# 8085.net
KiCad netlist of a schematic drawn in EAGLE
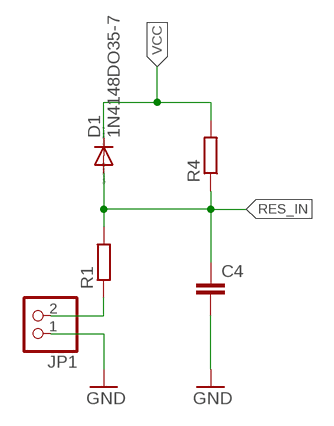
[diagram p0: schematic, sheet 1, part 1 of 3]
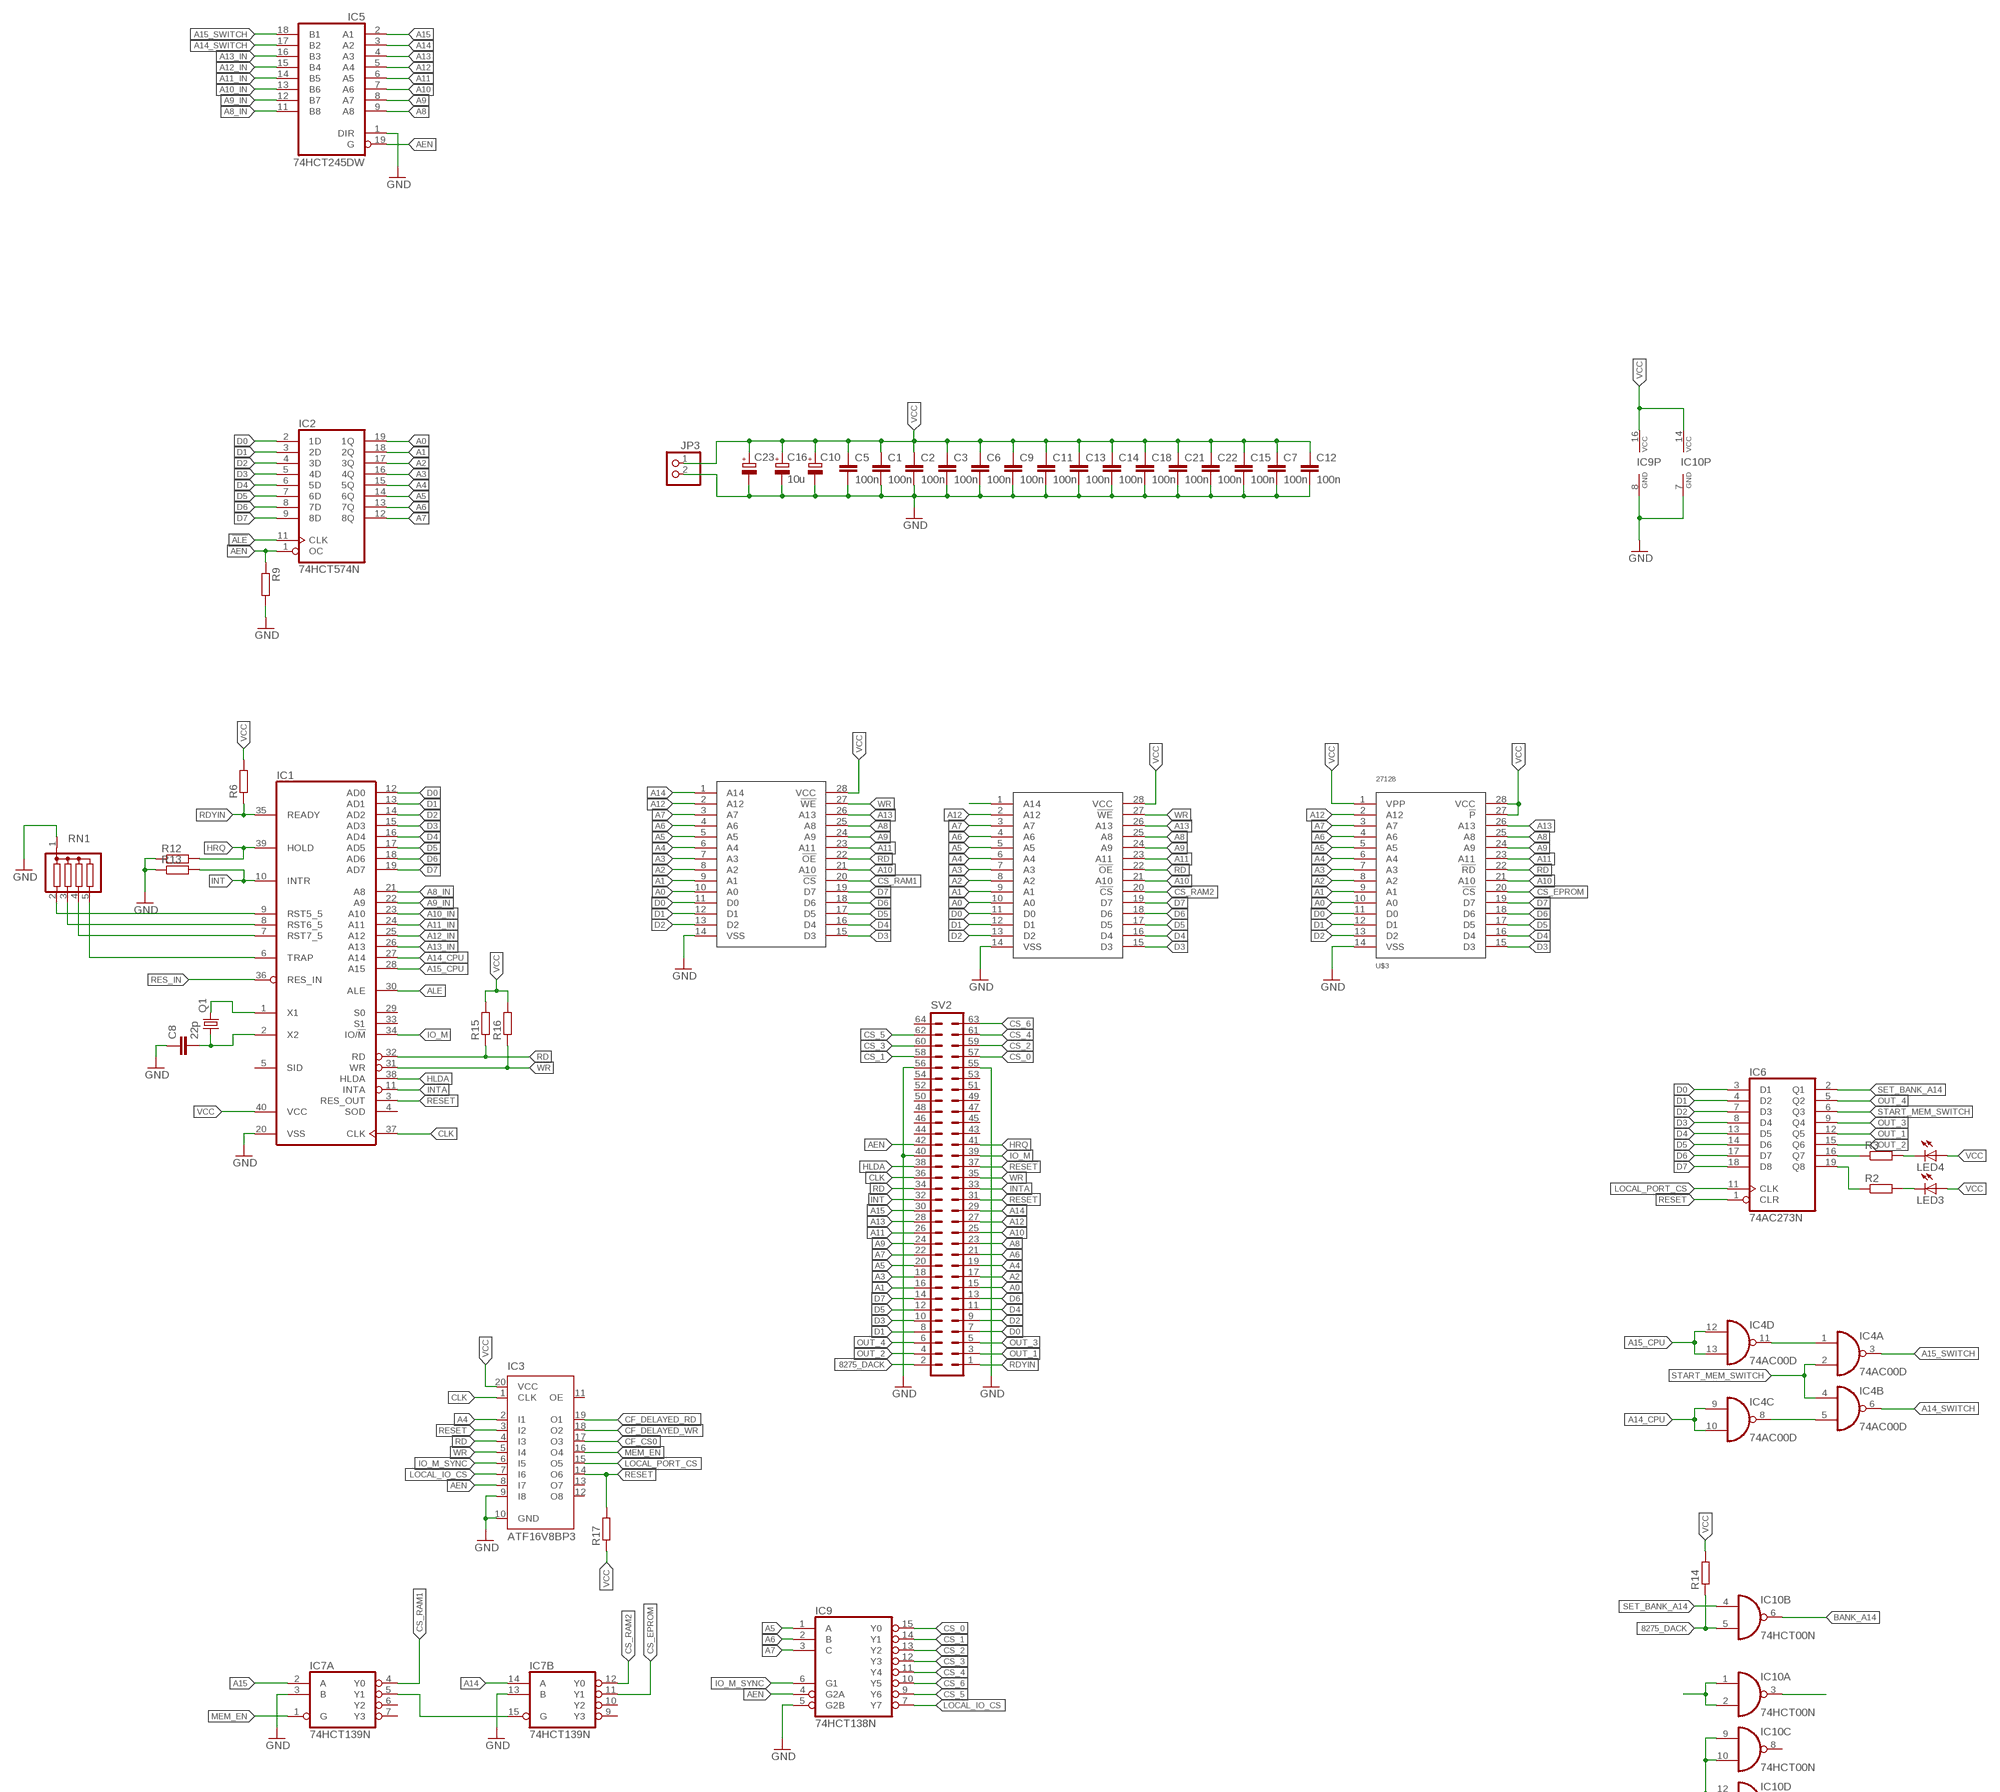
[diagram p1: schematic, sheet 1, part 2 of 3]
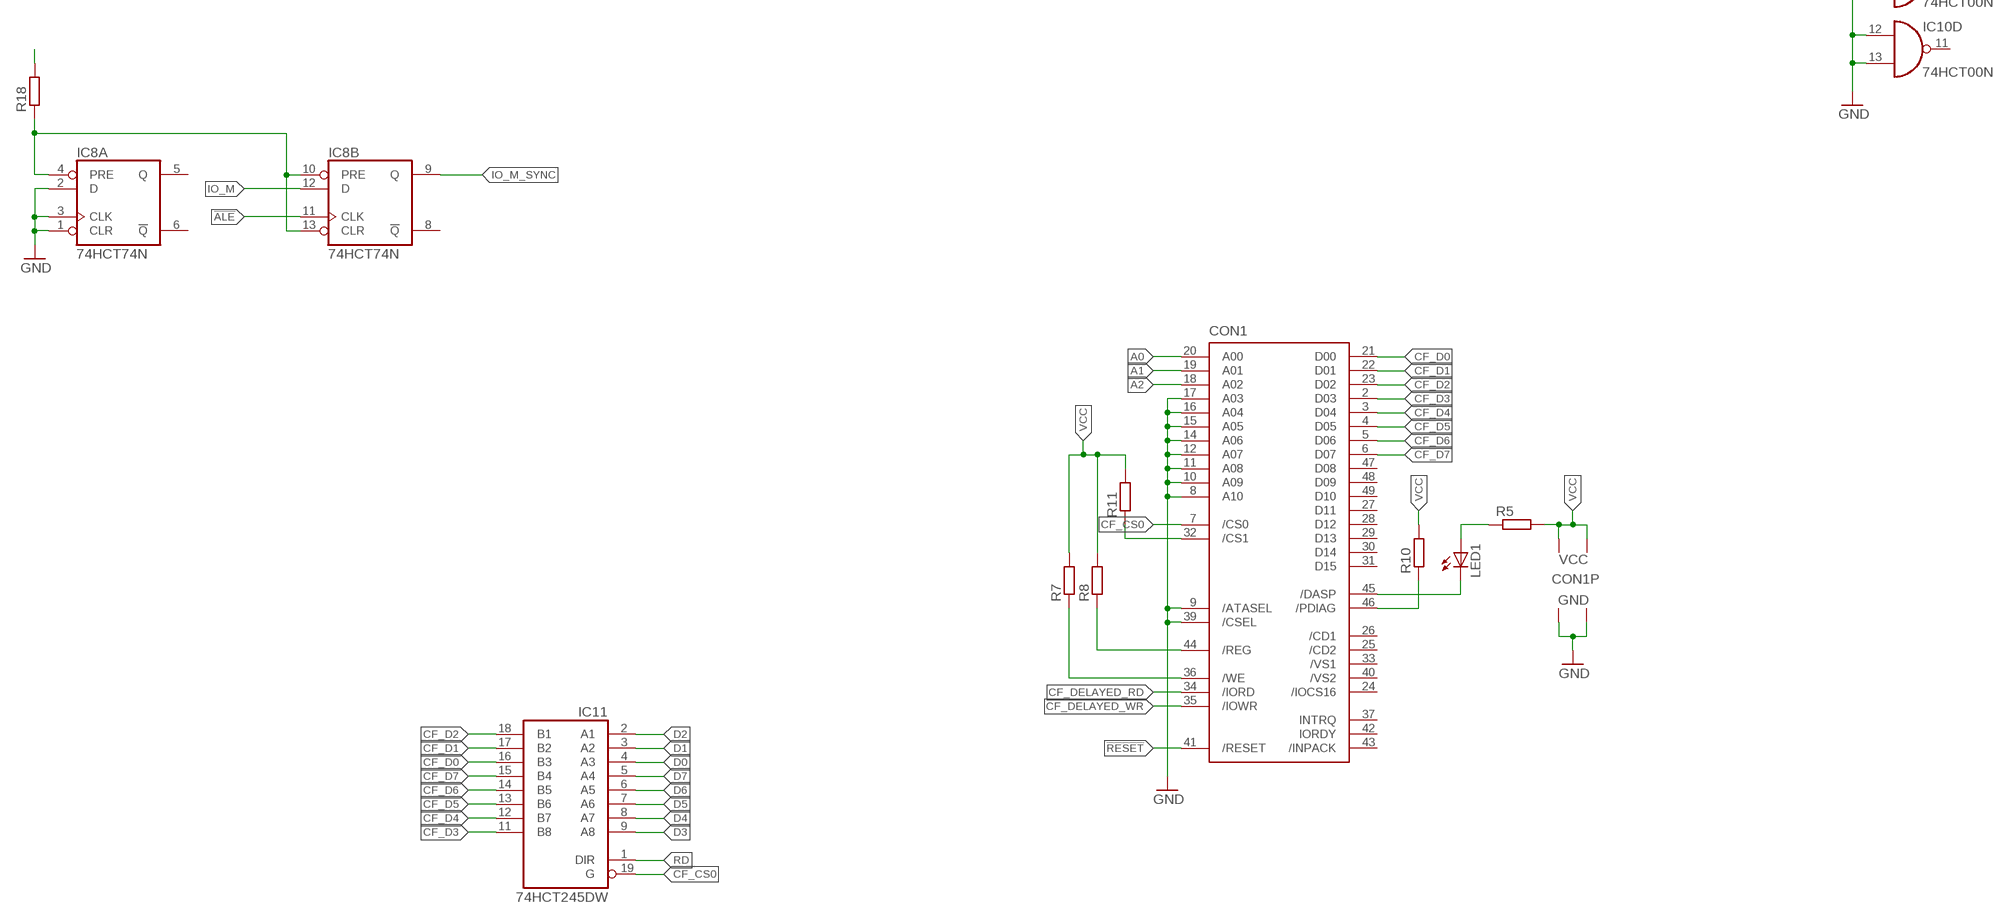
[diagram p2: schematic, sheet 1, part 3 of 3]

(export (version "E")
  (design (tool "Eeschema 10.0.6"))
  (components
    (comp (ref "C1")
      (value "100n")
      (footprint "eagle-import:C0805")
      (libsource (lib "eagle-import") (part "C-EUC0805"))
    )
    (comp (ref "C2")
      (value "100n")
      (footprint "eagle-import:C0805")
      (libsource (lib "eagle-import") (part "C-EUC0805"))
    )
    (comp (ref "C3")
      (value "100n")
      (footprint "eagle-import:C0805")
      (libsource (lib "eagle-import") (part "C-EUC0805"))
    )
    (comp (ref "C4")
      (value "C-EUC0603")
      (footprint "eagle-import:C0603")
      (libsource (lib "eagle-import") (part "C-EUC0603"))
    )
    (comp (ref "C5")
      (value "100n")
      (footprint "eagle-import:C0603")
      (libsource (lib "eagle-import") (part "C-EUC0603"))
    )
    (comp (ref "C6")
      (value "100n")
      (footprint "eagle-import:C0805")
      (libsource (lib "eagle-import") (part "C-EUC0805"))
    )
    (comp (ref "C7")
      (value "100n")
      (footprint "eagle-import:C0603")
      (libsource (lib "eagle-import") (part "C-EUC0603"))
    )
    (comp (ref "C8")
      (value "22p")
      (footprint "eagle-import:C0603")
      (libsource (lib "eagle-import") (part "C-EUC0603"))
    )
    (comp (ref "C9")
      (value "100n")
      (footprint "eagle-import:C1206")
      (libsource (lib "eagle-import") (part "C-EUC1206"))
    )
    (comp (ref "C10")
      (value "CPOL-EUE5-10.5")
      (footprint "eagle-import:E5-10,5")
      (libsource (lib "eagle-import") (part "CPOL-EUE5-10.5"))
    )
    (comp (ref "C11")
      (value "100n")
      (footprint "eagle-import:C0805")
      (libsource (lib "eagle-import") (part "C-EUC0805"))
    )
    (comp (ref "C12")
      (value "100n")
      (footprint "eagle-import:C0805")
      (libsource (lib "eagle-import") (part "C-EUC0805"))
    )
    (comp (ref "C13")
      (value "100n")
      (footprint "eagle-import:C0805")
      (libsource (lib "eagle-import") (part "C-EUC0805"))
    )
    (comp (ref "C14")
      (value "100n")
      (footprint "eagle-import:C0805")
      (libsource (lib "eagle-import") (part "C-EUC0805"))
    )
    (comp (ref "C15")
      (value "100n")
      (footprint "eagle-import:C1206")
      (libsource (lib "eagle-import") (part "C-EUC1206"))
    )
    (comp (ref "C16")
      (value "10u")
      (footprint "eagle-import:SMC_B")
      (libsource (lib "eagle-import") (part "CPOL-EUSMCB"))
    )
    (comp (ref "C18")
      (value "100n")
      (footprint "eagle-import:C0603")
      (libsource (lib "eagle-import") (part "C-EUC0603"))
    )
    (comp (ref "C21")
      (value "100n")
      (footprint "eagle-import:C0603")
      (libsource (lib "eagle-import") (part "C-EUC0603"))
    )
    (comp (ref "C22")
      (value "100n")
      (footprint "eagle-import:C0603")
      (libsource (lib "eagle-import") (part "C-EUC0603"))
    )
    (comp (ref "C23")
      (value "CPOL-EUE5-10.5")
      (footprint "eagle-import:E5-10,5")
      (libsource (lib "eagle-import") (part "CPOL-EUE5-10.5"))
    )
    (comp (ref "CON1")
      (value "CF-CARD-IDE_MODE")
      (footprint "eagle-import:MI20-50PD-SF")
      (libsource (lib "eagle-import") (part "CF-CARD-IDE_MODE"))
    )
    (comp (ref "D1")
      (value "1N4148DO35-7")
      (footprint "eagle-import:DO35-7")
      (libsource (lib "eagle-import") (part "1N4148DO35-7"))
    )
    (comp (ref "IC1")
      (value "8085")
      (footprint "eagle-import:DIL40")
      (libsource (lib "eagle-import") (part "8085"))
    )
    (comp (ref "IC2")
      (value "74HCT574N")
      (footprint "eagle-import:DIL20")
      (libsource (lib "eagle-import") (part "74574NHCT"))
    )
    (comp (ref "IC3")
      (value "ATF16V8BP3")
      (footprint "eagle-import:DIL20")
      (fields (field (name "MPN") "ATF16V8CZ-15PU"))
      (libsource (lib "eagle-import") (part "ATF16V8BP3"))
    )
    (comp (ref "IC4")
      (value "74AC00D")
      (footprint "eagle-import:SO14")
      (libsource (lib "eagle-import") (part "7400DAC"))
    )
    (comp (ref "IC5")
      (value "74HCT245DW")
      (footprint "eagle-import:SO20W")
      (libsource (lib "eagle-import") (part "74245DWHCT"))
    )
    (comp (ref "IC6")
      (value "74AC273N")
      (footprint "eagle-import:DIL20")
      (libsource (lib "eagle-import") (part "74273NAC"))
    )
    (comp (ref "IC7")
      (value "74HCT139N")
      (footprint "eagle-import:DIL16")
      (libsource (lib "eagle-import") (part "74139NHCT"))
    )
    (comp (ref "IC8")
      (value "74HCT74N")
      (footprint "eagle-import:DIL14")
      (libsource (lib "eagle-import") (part "7474NHCT"))
    )
    (comp (ref "IC9")
      (value "74HCT138N")
      (footprint "eagle-import:DIL16")
      (libsource (lib "eagle-import") (part "74138NHCT"))
    )
    (comp (ref "IC10")
      (value "74HCT00N")
      (footprint "eagle-import:DIL14")
      (libsource (lib "eagle-import") (part "7400NHCT"))
    )
    (comp (ref "IC11")
      (value "74HCT245DW")
      (footprint "eagle-import:SO20W")
      (libsource (lib "eagle-import") (part "74245DWHCT"))
    )
    (comp (ref "JP1")
      (value "PINHD-1X2")
      (footprint "eagle-import:1X02")
      (libsource (lib "eagle-import") (part "PINHD-1X2"))
    )
    (comp (ref "JP3")
      (value "PINHD-1X2")
      (footprint "eagle-import:1X02")
      (libsource (lib "eagle-import") (part "PINHD-1X2"))
    )
    (comp (ref "LED1")
      (value "LED5MM")
      (footprint "eagle-import:LED5MM")
      (libsource (lib "eagle-import") (part "LED5MM"))
    )
    (comp (ref "LED3")
      (value "LED5MM")
      (footprint "eagle-import:LED5MM")
      (libsource (lib "eagle-import") (part "LED5MM"))
    )
    (comp (ref "LED4")
      (value "LED5MM")
      (footprint "eagle-import:LED5MM")
      (libsource (lib "eagle-import") (part "LED5MM"))
    )
    (comp (ref "Q1")
      (value "CRYSTALHC49S")
      (footprint "eagle-import:HC49_S")
      (libsource (lib "eagle-import") (part "CRYSTALHC49S"))
    )
    (comp (ref "R1")
      (value "R-EU_0204/5")
      (footprint "eagle-import:0204_5")
      (libsource (lib "eagle-import") (part "R-EU_0204/5"))
    )
    (comp (ref "R2")
      (value "R-EU_R1206")
      (footprint "eagle-import:R1206")
      (libsource (lib "eagle-import") (part "R-EU_R1206"))
    )
    (comp (ref "R3")
      (value "R-EU_R1206")
      (footprint "eagle-import:R1206")
      (libsource (lib "eagle-import") (part "R-EU_R1206"))
    )
    (comp (ref "R4")
      (value "R-EU_0204/7")
      (footprint "eagle-import:0204_7")
      (libsource (lib "eagle-import") (part "R-EU_0204/7"))
    )
    (comp (ref "R5")
      (value "R-EU_R0603")
      (footprint "eagle-import:R0603")
      (libsource (lib "eagle-import") (part "R-EU_R0603"))
    )
    (comp (ref "R6")
      (value "R-EU_0204/5")
      (footprint "eagle-import:0204_5")
      (libsource (lib "eagle-import") (part "R-EU_0204/5"))
    )
    (comp (ref "R7")
      (value "R-EU_0207/10")
      (footprint "eagle-import:0207_10")
      (libsource (lib "eagle-import") (part "R-EU_0207/10"))
    )
    (comp (ref "R8")
      (value "R-EU_0207/12")
      (footprint "eagle-import:0207_12")
      (libsource (lib "eagle-import") (part "R-EU_0207/12"))
    )
    (comp (ref "R9")
      (value "R-EU_R0603")
      (footprint "eagle-import:R0603")
      (libsource (lib "eagle-import") (part "R-EU_R0603"))
    )
    (comp (ref "R10")
      (value "R-EU_0207/12")
      (footprint "eagle-import:0207_12")
      (libsource (lib "eagle-import") (part "R-EU_0207/12"))
    )
    (comp (ref "R11")
      (value "R-EU_0207/10")
      (footprint "eagle-import:0207_10")
      (libsource (lib "eagle-import") (part "R-EU_0207/10"))
    )
    (comp (ref "R12")
      (value "R-EU_R0603")
      (footprint "eagle-import:R0603")
      (libsource (lib "eagle-import") (part "R-EU_R0603"))
    )
    (comp (ref "R13")
      (value "R-EU_R0603")
      (footprint "eagle-import:R0603")
      (libsource (lib "eagle-import") (part "R-EU_R0603"))
    )
    (comp (ref "R14")
      (value "R-EU_0204/7")
      (footprint "eagle-import:0204_7")
      (libsource (lib "eagle-import") (part "R-EU_0204/7"))
    )
    (comp (ref "R15")
      (value "R-EU_0204/7")
      (footprint "eagle-import:0204_7")
      (libsource (lib "eagle-import") (part "R-EU_0204/7"))
    )
    (comp (ref "R16")
      (value "R-EU_0204/7")
      (footprint "eagle-import:0204_7")
      (libsource (lib "eagle-import") (part "R-EU_0204/7"))
    )
    (comp (ref "R17")
      (value "R-EU_0204/7")
      (footprint "eagle-import:0204_7")
      (libsource (lib "eagle-import") (part "R-EU_0204/7"))
    )
    (comp (ref "R18")
      (value "R-EU_0204/5")
      (footprint "eagle-import:0204_5")
      (libsource (lib "eagle-import") (part "R-EU_0204/5"))
    )
    (comp (ref "RN1")
      (value "G04R")
      (footprint "eagle-import:SIL5")
      (libsource (lib "eagle-import") (part "G04R"))
    )
    (comp (ref "SV2")
      (value "ML64L")
      (footprint "eagle-import:ML64L")
      (libsource (lib "eagle-import") (part "ML64L"))
    )
    (comp (ref "U$2")
      (value "62256")
      (footprint "eagle-import:DIL28-6")
      (libsource (lib "eagle-import") (part "62256"))
    )
    (comp (ref "U$3")
      (value "27128")
      (footprint "eagle-import:DIL28")
      (libsource (lib "eagle-import") (part "27128"))
    )
    (comp (ref "U$4")
      (value "62256")
      (footprint "eagle-import:DIL28-6")
      (libsource (lib "eagle-import") (part "62256"))
    )
  )
  (nets
    (net (code "1") (name "/~{ALE}") (class "Default")
      (node (ref "IC10") (pin "3") (pinfunction "O_3") (pintype "output"))
      (node (ref "IC2") (pin "11") (pinfunction "CLK_11") (pintype "input"))
      (node (ref "IC8") (pin "11") (pinfunction "CLK_11") (pintype "input"))
    )
    (net (code "2") (name "/~{RESET}") (class "Default")
      (node (ref "CON1") (pin "41") (pinfunction "/RESET_41") (pintype "input"))
      (node (ref "IC3") (pin "14") (pinfunction "O6_14") (pintype "output"))
      (node (ref "IC6") (pin "1") (pinfunction "CLR_1") (pintype "input"))
      (node (ref "R17") (pin "2") (pinfunction "2_2") (pintype "passive"))
      (node (ref "SV2") (pin "37") (pinfunction "37_37") (pintype "passive"))
    )
    (net (code "3") (name "8275_DACK") (class "Default")
      (node (ref "IC10") (pin "5") (pinfunction "I1_5") (pintype "input"))
      (node (ref "R14") (pin "1") (pinfunction "1_1") (pintype "passive"))
      (node (ref "SV2") (pin "2") (pinfunction "2_2") (pintype "passive"))
    )
    (net (code "4") (name "A0") (class "Default")
      (node (ref "CON1") (pin "20") (pinfunction "A00_20") (pintype "input"))
      (node (ref "IC2") (pin "19") (pinfunction "1Q_19") (pintype "tri_state"))
      (node (ref "SV2") (pin "15") (pinfunction "15_15") (pintype "passive"))
      (node (ref "U$2") (pin "10") (pinfunction "A0_10") (pintype "bidirectional"))
      (node (ref "U$3") (pin "10") (pinfunction "A0_10") (pintype "bidirectional"))
      (node (ref "U$4") (pin "10") (pinfunction "A0_10") (pintype "bidirectional"))
    )
    (net (code "5") (name "A1") (class "Default")
      (node (ref "CON1") (pin "19") (pinfunction "A01_19") (pintype "input"))
      (node (ref "IC2") (pin "18") (pinfunction "2Q_18") (pintype "tri_state"))
      (node (ref "SV2") (pin "16") (pinfunction "16_16") (pintype "passive"))
      (node (ref "U$2") (pin "9") (pinfunction "A1_9") (pintype "bidirectional"))
      (node (ref "U$3") (pin "9") (pinfunction "A1_9") (pintype "bidirectional"))
      (node (ref "U$4") (pin "9") (pinfunction "A1_9") (pintype "bidirectional"))
    )
    (net (code "6") (name "A2") (class "Default")
      (node (ref "CON1") (pin "18") (pinfunction "A02_18") (pintype "input"))
      (node (ref "IC2") (pin "17") (pinfunction "3Q_17") (pintype "tri_state"))
      (node (ref "SV2") (pin "17") (pinfunction "17_17") (pintype "passive"))
      (node (ref "U$2") (pin "8") (pinfunction "A2_8") (pintype "bidirectional"))
      (node (ref "U$3") (pin "8") (pinfunction "A2_8") (pintype "bidirectional"))
      (node (ref "U$4") (pin "8") (pinfunction "A2_8") (pintype "bidirectional"))
    )
    (net (code "7") (name "A3") (class "Default")
      (node (ref "IC2") (pin "16") (pinfunction "4Q_16") (pintype "tri_state"))
      (node (ref "SV2") (pin "18") (pinfunction "18_18") (pintype "passive"))
      (node (ref "U$2") (pin "7") (pinfunction "A3_7") (pintype "bidirectional"))
      (node (ref "U$3") (pin "7") (pinfunction "A3_7") (pintype "bidirectional"))
      (node (ref "U$4") (pin "7") (pinfunction "A3_7") (pintype "bidirectional"))
    )
    (net (code "8") (name "A4") (class "Default")
      (node (ref "IC2") (pin "15") (pinfunction "5Q_15") (pintype "tri_state"))
      (node (ref "IC3") (pin "2") (pinfunction "I1_2") (pintype "input"))
      (node (ref "SV2") (pin "19") (pinfunction "19_19") (pintype "passive"))
      (node (ref "U$2") (pin "6") (pinfunction "A4_6") (pintype "bidirectional"))
      (node (ref "U$3") (pin "6") (pinfunction "A4_6") (pintype "bidirectional"))
      (node (ref "U$4") (pin "6") (pinfunction "A4_6") (pintype "bidirectional"))
    )
    (net (code "9") (name "A5") (class "Default")
      (node (ref "IC2") (pin "14") (pinfunction "6Q_14") (pintype "tri_state"))
      (node (ref "IC9") (pin "1") (pinfunction "A_1") (pintype "input"))
      (node (ref "SV2") (pin "20") (pinfunction "20_20") (pintype "passive"))
      (node (ref "U$2") (pin "5") (pinfunction "A5_5") (pintype "bidirectional"))
      (node (ref "U$3") (pin "5") (pinfunction "A5_5") (pintype "bidirectional"))
      (node (ref "U$4") (pin "5") (pinfunction "A5_5") (pintype "bidirectional"))
    )
    (net (code "10") (name "A6") (class "Default")
      (node (ref "IC2") (pin "13") (pinfunction "7Q_13") (pintype "tri_state"))
      (node (ref "IC9") (pin "2") (pinfunction "B_2") (pintype "input"))
      (node (ref "SV2") (pin "21") (pinfunction "21_21") (pintype "passive"))
      (node (ref "U$2") (pin "4") (pinfunction "A6_4") (pintype "bidirectional"))
      (node (ref "U$3") (pin "4") (pinfunction "A6_4") (pintype "bidirectional"))
      (node (ref "U$4") (pin "4") (pinfunction "A6_4") (pintype "bidirectional"))
    )
    (net (code "11") (name "A7") (class "Default")
      (node (ref "IC2") (pin "12") (pinfunction "8Q_12") (pintype "tri_state"))
      (node (ref "IC9") (pin "3") (pinfunction "C_3") (pintype "input"))
      (node (ref "SV2") (pin "22") (pinfunction "22_22") (pintype "passive"))
      (node (ref "U$2") (pin "3") (pinfunction "A7_3") (pintype "bidirectional"))
      (node (ref "U$3") (pin "3") (pinfunction "A7_3") (pintype "bidirectional"))
      (node (ref "U$4") (pin "3") (pinfunction "A7_3") (pintype "bidirectional"))
    )
    (net (code "12") (name "A8") (class "Default")
      (node (ref "IC5") (pin "9") (pinfunction "A8_9") (pintype "bidirectional"))
      (node (ref "SV2") (pin "23") (pinfunction "23_23") (pintype "passive"))
      (node (ref "U$2") (pin "25") (pinfunction "A8_25") (pintype "bidirectional"))
      (node (ref "U$3") (pin "25") (pinfunction "A8_25") (pintype "bidirectional"))
      (node (ref "U$4") (pin "25") (pinfunction "A8_25") (pintype "bidirectional"))
    )
    (net (code "13") (name "A8_IN") (class "Default")
      (node (ref "IC1") (pin "21") (pinfunction "A8_21") (pintype "output"))
      (node (ref "IC5") (pin "11") (pinfunction "B8_11") (pintype "bidirectional"))
    )
    (net (code "14") (name "A9") (class "Default")
      (node (ref "IC5") (pin "8") (pinfunction "A7_8") (pintype "bidirectional"))
      (node (ref "SV2") (pin "24") (pinfunction "24_24") (pintype "passive"))
      (node (ref "U$2") (pin "24") (pinfunction "A9_24") (pintype "bidirectional"))
      (node (ref "U$3") (pin "24") (pinfunction "A9_24") (pintype "bidirectional"))
      (node (ref "U$4") (pin "24") (pinfunction "A9_24") (pintype "bidirectional"))
    )
    (net (code "15") (name "A9_IN") (class "Default")
      (node (ref "IC1") (pin "22") (pinfunction "A9_22") (pintype "output"))
      (node (ref "IC5") (pin "12") (pinfunction "B7_12") (pintype "bidirectional"))
    )
    (net (code "16") (name "A10") (class "Default")
      (node (ref "IC5") (pin "7") (pinfunction "A6_7") (pintype "bidirectional"))
      (node (ref "SV2") (pin "25") (pinfunction "25_25") (pintype "passive"))
      (node (ref "U$2") (pin "21") (pinfunction "A10_21") (pintype "bidirectional"))
      (node (ref "U$3") (pin "21") (pinfunction "A10_21") (pintype "bidirectional"))
      (node (ref "U$4") (pin "21") (pinfunction "A10_21") (pintype "bidirectional"))
    )
    (net (code "17") (name "A10_IN") (class "Default")
      (node (ref "IC1") (pin "23") (pinfunction "A10_23") (pintype "output"))
      (node (ref "IC5") (pin "13") (pinfunction "B6_13") (pintype "bidirectional"))
    )
    (net (code "18") (name "A11") (class "Default")
      (node (ref "IC5") (pin "6") (pinfunction "A5_6") (pintype "bidirectional"))
      (node (ref "SV2") (pin "26") (pinfunction "26_26") (pintype "passive"))
      (node (ref "U$2") (pin "23") (pinfunction "A11_23") (pintype "bidirectional"))
      (node (ref "U$3") (pin "23") (pinfunction "A11_23") (pintype "bidirectional"))
      (node (ref "U$4") (pin "23") (pinfunction "A11_23") (pintype "bidirectional"))
    )
    (net (code "19") (name "A11_IN") (class "Default")
      (node (ref "IC1") (pin "24") (pinfunction "A11_24") (pintype "output"))
      (node (ref "IC5") (pin "14") (pinfunction "B5_14") (pintype "bidirectional"))
    )
    (net (code "20") (name "A12") (class "Default")
      (node (ref "IC5") (pin "5") (pinfunction "A4_5") (pintype "bidirectional"))
      (node (ref "SV2") (pin "27") (pinfunction "27_27") (pintype "passive"))
      (node (ref "U$2") (pin "2") (pinfunction "A12_2") (pintype "bidirectional"))
      (node (ref "U$3") (pin "2") (pinfunction "A12_2") (pintype "bidirectional"))
      (node (ref "U$4") (pin "2") (pinfunction "A12_2") (pintype "bidirectional"))
    )
    (net (code "21") (name "A12_IN") (class "Default")
      (node (ref "IC1") (pin "25") (pinfunction "A12_25") (pintype "output"))
      (node (ref "IC5") (pin "15") (pinfunction "B4_15") (pintype "bidirectional"))
    )
    (net (code "22") (name "A13") (class "Default")
      (node (ref "IC5") (pin "4") (pinfunction "A3_4") (pintype "bidirectional"))
      (node (ref "SV2") (pin "28") (pinfunction "28_28") (pintype "passive"))
      (node (ref "U$2") (pin "26") (pinfunction "A13_26") (pintype "bidirectional"))
      (node (ref "U$3") (pin "26") (pinfunction "A13_26") (pintype "bidirectional"))
      (node (ref "U$4") (pin "26") (pinfunction "A13_26") (pintype "bidirectional"))
    )
    (net (code "23") (name "A13_IN") (class "Default")
      (node (ref "IC1") (pin "26") (pinfunction "A13_26") (pintype "output"))
      (node (ref "IC5") (pin "16") (pinfunction "B3_16") (pintype "bidirectional"))
    )
    (net (code "24") (name "A14") (class "Default")
      (node (ref "IC5") (pin "3") (pinfunction "A2_3") (pintype "bidirectional"))
      (node (ref "IC7") (pin "14") (pinfunction "A_14") (pintype "input"))
      (node (ref "SV2") (pin "29") (pinfunction "29_29") (pintype "passive"))
      (node (ref "U$4") (pin "1") (pinfunction "A14_1") (pintype "bidirectional"))
    )
    (net (code "25") (name "A14_CPU") (class "Default")
      (node (ref "IC1") (pin "27") (pinfunction "A14_27") (pintype "output"))
      (node (ref "IC4") (pin "10") (pinfunction "I1_10") (pintype "input"))
      (node (ref "IC4") (pin "9") (pinfunction "I0_9") (pintype "input"))
    )
    (net (code "26") (name "A14_SWITCH") (class "Default")
      (node (ref "IC4") (pin "6") (pinfunction "O_6") (pintype "output"))
      (node (ref "IC5") (pin "17") (pinfunction "B2_17") (pintype "bidirectional"))
    )
    (net (code "27") (name "A15") (class "Default")
      (node (ref "IC5") (pin "2") (pinfunction "A1_2") (pintype "bidirectional"))
      (node (ref "IC7") (pin "2") (pinfunction "A_2") (pintype "input"))
      (node (ref "SV2") (pin "30") (pinfunction "30_30") (pintype "passive"))
    )
    (net (code "28") (name "A15_CPU") (class "Default")
      (node (ref "IC1") (pin "28") (pinfunction "A15_28") (pintype "output"))
      (node (ref "IC4") (pin "12") (pinfunction "I0_12") (pintype "input"))
      (node (ref "IC4") (pin "13") (pinfunction "I1_13") (pintype "input"))
    )
    (net (code "29") (name "A15_SWITCH") (class "Default")
      (node (ref "IC4") (pin "3") (pinfunction "O_3") (pintype "output"))
      (node (ref "IC5") (pin "18") (pinfunction "B1_18") (pintype "bidirectional"))
    )
    (net (code "30") (name "AEN") (class "Default")
      (node (ref "IC2") (pin "1") (pinfunction "OC_1") (pintype "input"))
      (node (ref "IC3") (pin "8") (pinfunction "I7_8") (pintype "input"))
      (node (ref "IC5") (pin "19") (pinfunction "G_19") (pintype "input"))
      (node (ref "IC9") (pin "4") (pinfunction "G2A_4") (pintype "input"))
      (node (ref "R9") (pin "1") (pinfunction "1_1") (pintype "passive"))
      (node (ref "SV2") (pin "42") (pinfunction "42_42") (pintype "passive"))
    )
    (net (code "31") (name "ALE") (class "Default")
      (node (ref "IC1") (pin "30") (pinfunction "ALE_30") (pintype "output"))
      (node (ref "IC10") (pin "1") (pinfunction "I0_1") (pintype "input"))
      (node (ref "IC10") (pin "2") (pinfunction "I1_2") (pintype "input"))
    )
    (net (code "32") (name "BANK_A14") (class "Default")
      (node (ref "IC10") (pin "6") (pinfunction "O_6") (pintype "output"))
      (node (ref "U$2") (pin "1") (pinfunction "A14_1") (pintype "bidirectional"))
    )
    (net (code "33") (name "CF_CS0") (class "Default")
      (node (ref "CON1") (pin "7") (pinfunction "/CS0_7") (pintype "input"))
      (node (ref "IC11") (pin "19") (pinfunction "G_19") (pintype "input"))
      (node (ref "IC3") (pin "17") (pinfunction "O3_17") (pintype "output"))
    )
    (net (code "34") (name "CF_D0") (class "Default")
      (node (ref "CON1") (pin "21") (pinfunction "D00_21") (pintype "bidirectional"))
      (node (ref "IC11") (pin "16") (pinfunction "B3_16") (pintype "bidirectional"))
    )
    (net (code "35") (name "CF_D1") (class "Default")
      (node (ref "CON1") (pin "22") (pinfunction "D01_22") (pintype "bidirectional"))
      (node (ref "IC11") (pin "17") (pinfunction "B2_17") (pintype "bidirectional"))
    )
    (net (code "36") (name "CF_D2") (class "Default")
      (node (ref "CON1") (pin "23") (pinfunction "D02_23") (pintype "bidirectional"))
      (node (ref "IC11") (pin "18") (pinfunction "B1_18") (pintype "bidirectional"))
    )
    (net (code "37") (name "CF_D3") (class "Default")
      (node (ref "CON1") (pin "2") (pinfunction "D03_2") (pintype "bidirectional"))
      (node (ref "IC11") (pin "11") (pinfunction "B8_11") (pintype "bidirectional"))
    )
    (net (code "38") (name "CF_D4") (class "Default")
      (node (ref "CON1") (pin "3") (pinfunction "D04_3") (pintype "bidirectional"))
      (node (ref "IC11") (pin "12") (pinfunction "B7_12") (pintype "bidirectional"))
    )
    (net (code "39") (name "CF_D5") (class "Default")
      (node (ref "CON1") (pin "4") (pinfunction "D05_4") (pintype "bidirectional"))
      (node (ref "IC11") (pin "13") (pinfunction "B6_13") (pintype "bidirectional"))
    )
    (net (code "40") (name "CF_D6") (class "Default")
      (node (ref "CON1") (pin "5") (pinfunction "D06_5") (pintype "bidirectional"))
      (node (ref "IC11") (pin "14") (pinfunction "B5_14") (pintype "bidirectional"))
    )
    (net (code "41") (name "CF_D7") (class "Default")
      (node (ref "CON1") (pin "6") (pinfunction "D07_6") (pintype "bidirectional"))
      (node (ref "IC11") (pin "15") (pinfunction "B4_15") (pintype "bidirectional"))
    )
    (net (code "42") (name "CF_DELAYED_RD") (class "Default")
      (node (ref "CON1") (pin "34") (pinfunction "/IORD_34") (pintype "input"))
      (node (ref "IC3") (pin "19") (pinfunction "O1_19") (pintype "output"))
    )
    (net (code "43") (name "CF_DELAYED_WR") (class "Default")
      (node (ref "CON1") (pin "35") (pinfunction "/IOWR_35") (pintype "input"))
      (node (ref "IC3") (pin "18") (pinfunction "O2_18") (pintype "output"))
    )
    (net (code "44") (name "CLK") (class "Default")
      (node (ref "IC1") (pin "37") (pinfunction "CLK_37") (pintype "output"))
      (node (ref "IC3") (pin "1") (pinfunction "CLK_1") (pintype "input"))
      (node (ref "SV2") (pin "36") (pinfunction "36_36") (pintype "passive"))
    )
    (net (code "45") (name "CS_0") (class "Default")
      (node (ref "IC9") (pin "15") (pinfunction "Y0_15") (pintype "output"))
      (node (ref "SV2") (pin "57") (pinfunction "57_57") (pintype "passive"))
    )
    (net (code "46") (name "CS_1") (class "Default")
      (node (ref "IC9") (pin "14") (pinfunction "Y1_14") (pintype "output"))
      (node (ref "SV2") (pin "58") (pinfunction "58_58") (pintype "passive"))
    )
    (net (code "47") (name "CS_2") (class "Default")
      (node (ref "IC9") (pin "13") (pinfunction "Y2_13") (pintype "output"))
      (node (ref "SV2") (pin "59") (pinfunction "59_59") (pintype "passive"))
    )
    (net (code "48") (name "CS_3") (class "Default")
      (node (ref "IC9") (pin "12") (pinfunction "Y3_12") (pintype "output"))
      (node (ref "SV2") (pin "60") (pinfunction "60_60") (pintype "passive"))
    )
    (net (code "49") (name "CS_4") (class "Default")
      (node (ref "IC9") (pin "11") (pinfunction "Y4_11") (pintype "output"))
      (node (ref "SV2") (pin "61") (pinfunction "61_61") (pintype "passive"))
    )
    (net (code "50") (name "CS_5") (class "Default")
      (node (ref "IC9") (pin "9") (pinfunction "Y6_9") (pintype "output"))
      (node (ref "SV2") (pin "62") (pinfunction "62_62") (pintype "passive"))
    )
    (net (code "51") (name "CS_6") (class "Default")
      (node (ref "IC9") (pin "10") (pinfunction "Y5_10") (pintype "output"))
      (node (ref "SV2") (pin "63") (pinfunction "63_63") (pintype "passive"))
    )
    (net (code "52") (name "CS_EPROM") (class "Default")
      (node (ref "IC7") (pin "11") (pinfunction "Y1_11") (pintype "output"))
      (node (ref "U$3") (pin "20") (pinfunction "~{CS}_20") (pintype "bidirectional"))
    )
    (net (code "53") (name "CS_RAM1") (class "Default")
      (node (ref "IC7") (pin "4") (pinfunction "Y0_4") (pintype "output"))
      (node (ref "U$4") (pin "20") (pinfunction "~{CS}_20") (pintype "bidirectional"))
    )
    (net (code "54") (name "CS_RAM2") (class "Default")
      (node (ref "IC7") (pin "12") (pinfunction "Y0_12") (pintype "output"))
      (node (ref "U$2") (pin "20") (pinfunction "~{CS}_20") (pintype "bidirectional"))
    )
    (net (code "55") (name "D0") (class "Default")
      (node (ref "IC1") (pin "12") (pinfunction "AD0_12") (pintype "bidirectional"))
      (node (ref "IC11") (pin "4") (pinfunction "A3_4") (pintype "bidirectional"))
      (node (ref "IC2") (pin "2") (pinfunction "1D_2") (pintype "input"))
      (node (ref "IC6") (pin "3") (pinfunction "D1_3") (pintype "input"))
      (node (ref "SV2") (pin "7") (pinfunction "7_7") (pintype "passive"))
      (node (ref "U$2") (pin "11") (pinfunction "D0_11") (pintype "bidirectional"))
      (node (ref "U$3") (pin "11") (pinfunction "D0_11") (pintype "bidirectional"))
      (node (ref "U$4") (pin "11") (pinfunction "D0_11") (pintype "bidirectional"))
    )
    (net (code "56") (name "D1") (class "Default")
      (node (ref "IC1") (pin "13") (pinfunction "AD1_13") (pintype "bidirectional"))
      (node (ref "IC11") (pin "3") (pinfunction "A2_3") (pintype "bidirectional"))
      (node (ref "IC2") (pin "3") (pinfunction "2D_3") (pintype "input"))
      (node (ref "IC6") (pin "4") (pinfunction "D2_4") (pintype "input"))
      (node (ref "SV2") (pin "8") (pinfunction "8_8") (pintype "passive"))
      (node (ref "U$2") (pin "12") (pinfunction "D1_12") (pintype "bidirectional"))
      (node (ref "U$3") (pin "12") (pinfunction "D1_12") (pintype "bidirectional"))
      (node (ref "U$4") (pin "12") (pinfunction "D1_12") (pintype "bidirectional"))
    )
    (net (code "57") (name "D2") (class "Default")
      (node (ref "IC1") (pin "14") (pinfunction "AD2_14") (pintype "bidirectional"))
      (node (ref "IC11") (pin "2") (pinfunction "A1_2") (pintype "bidirectional"))
      (node (ref "IC2") (pin "4") (pinfunction "3D_4") (pintype "input"))
      (node (ref "IC6") (pin "7") (pinfunction "D3_7") (pintype "input"))
      (node (ref "SV2") (pin "9") (pinfunction "9_9") (pintype "passive"))
      (node (ref "U$2") (pin "13") (pinfunction "D2_13") (pintype "bidirectional"))
      (node (ref "U$3") (pin "13") (pinfunction "D2_13") (pintype "bidirectional"))
      (node (ref "U$4") (pin "13") (pinfunction "D2_13") (pintype "bidirectional"))
    )
    (net (code "58") (name "D3") (class "Default")
      (node (ref "IC1") (pin "15") (pinfunction "AD3_15") (pintype "bidirectional"))
      (node (ref "IC11") (pin "9") (pinfunction "A8_9") (pintype "bidirectional"))
      (node (ref "IC2") (pin "5") (pinfunction "4D_5") (pintype "input"))
      (node (ref "IC6") (pin "8") (pinfunction "D4_8") (pintype "input"))
      (node (ref "SV2") (pin "10") (pinfunction "10_10") (pintype "passive"))
      (node (ref "U$2") (pin "15") (pinfunction "D3_15") (pintype "bidirectional"))
      (node (ref "U$3") (pin "15") (pinfunction "D3_15") (pintype "bidirectional"))
      (node (ref "U$4") (pin "15") (pinfunction "D3_15") (pintype "bidirectional"))
    )
    (net (code "59") (name "D4") (class "Default")
      (node (ref "IC1") (pin "16") (pinfunction "AD4_16") (pintype "bidirectional"))
      (node (ref "IC11") (pin "8") (pinfunction "A7_8") (pintype "bidirectional"))
      (node (ref "IC2") (pin "6") (pinfunction "5D_6") (pintype "input"))
      (node (ref "IC6") (pin "13") (pinfunction "D5_13") (pintype "input"))
      (node (ref "SV2") (pin "11") (pinfunction "11_11") (pintype "passive"))
      (node (ref "U$2") (pin "16") (pinfunction "D4_16") (pintype "bidirectional"))
      (node (ref "U$3") (pin "16") (pinfunction "D4_16") (pintype "bidirectional"))
      (node (ref "U$4") (pin "16") (pinfunction "D4_16") (pintype "bidirectional"))
    )
    (net (code "60") (name "D5") (class "Default")
      (node (ref "IC1") (pin "17") (pinfunction "AD5_17") (pintype "bidirectional"))
      (node (ref "IC11") (pin "7") (pinfunction "A6_7") (pintype "bidirectional"))
      (node (ref "IC2") (pin "7") (pinfunction "6D_7") (pintype "input"))
      (node (ref "IC6") (pin "14") (pinfunction "D6_14") (pintype "input"))
      (node (ref "SV2") (pin "12") (pinfunction "12_12") (pintype "passive"))
      (node (ref "U$2") (pin "17") (pinfunction "D5_17") (pintype "bidirectional"))
      (node (ref "U$3") (pin "17") (pinfunction "D5_17") (pintype "bidirectional"))
      (node (ref "U$4") (pin "17") (pinfunction "D5_17") (pintype "bidirectional"))
    )
    (net (code "61") (name "D6") (class "Default")
      (node (ref "IC1") (pin "18") (pinfunction "AD6_18") (pintype "bidirectional"))
      (node (ref "IC11") (pin "6") (pinfunction "A5_6") (pintype "bidirectional"))
      (node (ref "IC2") (pin "8") (pinfunction "7D_8") (pintype "input"))
      (node (ref "IC6") (pin "17") (pinfunction "D7_17") (pintype "input"))
      (node (ref "SV2") (pin "13") (pinfunction "13_13") (pintype "passive"))
      (node (ref "U$2") (pin "18") (pinfunction "D6_18") (pintype "bidirectional"))
      (node (ref "U$3") (pin "18") (pinfunction "D6_18") (pintype "bidirectional"))
      (node (ref "U$4") (pin "18") (pinfunction "D6_18") (pintype "bidirectional"))
    )
    (net (code "62") (name "D7") (class "Default")
      (node (ref "IC1") (pin "19") (pinfunction "AD7_19") (pintype "bidirectional"))
      (node (ref "IC11") (pin "5") (pinfunction "A4_5") (pintype "bidirectional"))
      (node (ref "IC2") (pin "9") (pinfunction "8D_9") (pintype "input"))
      (node (ref "IC6") (pin "18") (pinfunction "D8_18") (pintype "input"))
      (node (ref "SV2") (pin "14") (pinfunction "14_14") (pintype "passive"))
      (node (ref "U$2") (pin "19") (pinfunction "D7_19") (pintype "bidirectional"))
      (node (ref "U$3") (pin "19") (pinfunction "D7_19") (pintype "bidirectional"))
      (node (ref "U$4") (pin "19") (pinfunction "D7_19") (pintype "bidirectional"))
    )
    (net (code "63") (name "GND") (class "Default")
      (node (ref "C1") (pin "2") (pinfunction "2_2") (pintype "passive"))
      (node (ref "C10") (pin "-") (pinfunction "-_-") (pintype "passive"))
      (node (ref "C11") (pin "2") (pinfunction "2_2") (pintype "passive"))
      (node (ref "C12") (pin "2") (pinfunction "2_2") (pintype "passive"))
      (node (ref "C13") (pin "2") (pinfunction "2_2") (pintype "passive"))
      (node (ref "C14") (pin "2") (pinfunction "2_2") (pintype "passive"))
      (node (ref "C15") (pin "2") (pinfunction "2_2") (pintype "passive"))
      (node (ref "C16") (pin "-") (pinfunction "-_-") (pintype "passive"))
      (node (ref "C18") (pin "2") (pinfunction "2_2") (pintype "passive"))
      (node (ref "C2") (pin "2") (pinfunction "2_2") (pintype "passive"))
      (node (ref "C21") (pin "2") (pinfunction "2_2") (pintype "passive"))
      (node (ref "C22") (pin "2") (pinfunction "2_2") (pintype "passive"))
      (node (ref "C23") (pin "-") (pinfunction "-_-") (pintype "passive"))
      (node (ref "C3") (pin "2") (pinfunction "2_2") (pintype "passive"))
      (node (ref "C4") (pin "2") (pinfunction "2_2") (pintype "passive"))
      (node (ref "C5") (pin "2") (pinfunction "2_2") (pintype "passive"))
      (node (ref "C6") (pin "2") (pinfunction "2_2") (pintype "passive"))
      (node (ref "C7") (pin "2") (pinfunction "2_2") (pintype "passive"))
      (node (ref "C8") (pin "1") (pinfunction "1_1") (pintype "passive"))
      (node (ref "C9") (pin "2") (pinfunction "2_2") (pintype "passive"))
      (node (ref "CON1") (pin "1") (pinfunction "GND1_1") (pintype "power_in"))
      (node (ref "CON1") (pin "10") (pinfunction "A09_10") (pintype "input"))
      (node (ref "CON1") (pin "11") (pinfunction "A08_11") (pintype "input"))
      (node (ref "CON1") (pin "12") (pinfunction "A07_12") (pintype "input"))
      (node (ref "CON1") (pin "14") (pinfunction "A06_14") (pintype "input"))
      (node (ref "CON1") (pin "15") (pinfunction "A05_15") (pintype "input"))
      (node (ref "CON1") (pin "16") (pinfunction "A04_16") (pintype "input"))
      (node (ref "CON1") (pin "17") (pinfunction "A03_17") (pintype "input"))
      (node (ref "CON1") (pin "39") (pinfunction "/CSEL_39") (pintype "input"))
      (node (ref "CON1") (pin "50") (pinfunction "GND2_50") (pintype "power_in"))
      (node (ref "CON1") (pin "8") (pinfunction "A10_8") (pintype "input"))
      (node (ref "CON1") (pin "9") (pinfunction "/ATASEL_9") (pintype "input"))
      (node (ref "IC1") (pin "20") (pinfunction "VSS_20") (pintype "power_in"))
      (node (ref "IC10") (pin "10") (pinfunction "I1_10") (pintype "input"))
      (node (ref "IC10") (pin "12") (pinfunction "I0_12") (pintype "input"))
      (node (ref "IC10") (pin "13") (pinfunction "I1_13") (pintype "input"))
      (node (ref "IC10") (pin "7") (pinfunction "GND_7") (pintype "power_in"))
      (node (ref "IC10") (pin "9") (pinfunction "I0_9") (pintype "input"))
      (node (ref "IC3") (pin "10") (pinfunction "GND_10") (pintype "power_in"))
      (node (ref "IC3") (pin "9") (pinfunction "I8_9") (pintype "input"))
      (node (ref "IC5") (pin "1") (pinfunction "DIR_1") (pintype "input"))
      (node (ref "IC7") (pin "13") (pinfunction "B_13") (pintype "input"))
      (node (ref "IC7") (pin "3") (pinfunction "B_3") (pintype "input"))
      (node (ref "IC8") (pin "1") (pinfunction "CLR_1") (pintype "input"))
      (node (ref "IC8") (pin "2") (pinfunction "D_2") (pintype "input"))
      (node (ref "IC8") (pin "3") (pinfunction "CLK_3") (pintype "input"))
      (node (ref "IC9") (pin "5") (pinfunction "G2B_5") (pintype "input"))
      (node (ref "IC9") (pin "8") (pinfunction "GND_8") (pintype "power_in"))
      (node (ref "JP1") (pin "1") (pinfunction "1_1") (pintype "passive"))
      (node (ref "JP3") (pin "2") (pinfunction "2_2") (pintype "passive"))
      (node (ref "R12") (pin "1") (pinfunction "1_1") (pintype "passive"))
      (node (ref "R13") (pin "1") (pinfunction "1_1") (pintype "passive"))
      (node (ref "R9") (pin "2") (pinfunction "2_2") (pintype "passive"))
      (node (ref "RN1") (pin "1") (pinfunction "1_1") (pintype "passive"))
      (node (ref "SV2") (pin "40") (pinfunction "40_40") (pintype "passive"))
      (node (ref "SV2") (pin "55") (pinfunction "55_55") (pintype "passive"))
      (node (ref "SV2") (pin "56") (pinfunction "56_56") (pintype "passive"))
      (node (ref "U$2") (pin "14") (pinfunction "VSS_14") (pintype "bidirectional"))
      (node (ref "U$3") (pin "14") (pinfunction "VSS_14") (pintype "bidirectional"))
      (node (ref "U$4") (pin "14") (pinfunction "VSS_14") (pintype "bidirectional"))
    )
    (net (code "64") (name "HLDA") (class "Default")
      (node (ref "IC1") (pin "38") (pinfunction "HLDA_38") (pintype "output"))
      (node (ref "SV2") (pin "38") (pinfunction "38_38") (pintype "passive"))
    )
    (net (code "65") (name "HRQ") (class "Default")
      (node (ref "IC1") (pin "39") (pinfunction "HOLD_39") (pintype "input"))
      (node (ref "R12") (pin "2") (pinfunction "2_2") (pintype "passive"))
      (node (ref "SV2") (pin "41") (pinfunction "41_41") (pintype "passive"))
    )
    (net (code "66") (name "INT") (class "Default")
      (node (ref "IC1") (pin "10") (pinfunction "INTR_10") (pintype "input"))
      (node (ref "R13") (pin "2") (pinfunction "2_2") (pintype "passive"))
      (node (ref "SV2") (pin "32") (pinfunction "32_32") (pintype "passive"))
    )
    (net (code "67") (name "INTA") (class "Default")
      (node (ref "IC1") (pin "11") (pinfunction "INTA_11") (pintype "output"))
      (node (ref "SV2") (pin "33") (pinfunction "33_33") (pintype "passive"))
    )
    (net (code "68") (name "IO_M") (class "Default")
      (node (ref "IC1") (pin "34") (pinfunction "IO/~{M}_34") (pintype "output"))
      (node (ref "IC8") (pin "12") (pinfunction "D_12") (pintype "input"))
      (node (ref "SV2") (pin "39") (pinfunction "39_39") (pintype "passive"))
    )
    (net (code "69") (name "IO_M_SYNC") (class "Default")
      (node (ref "IC3") (pin "6") (pinfunction "I5_6") (pintype "input"))
      (node (ref "IC8") (pin "9") (pinfunction "Q_9") (pintype "output"))
      (node (ref "IC9") (pin "6") (pinfunction "G1_6") (pintype "input"))
    )
    (net (code "70") (name "LOCAL_IO_CS") (class "Default")
      (node (ref "IC3") (pin "7") (pinfunction "I6_7") (pintype "input"))
      (node (ref "IC9") (pin "7") (pinfunction "Y7_7") (pintype "output"))
    )
    (net (code "71") (name "LOCAL_PORT_CS") (class "Default")
      (node (ref "IC3") (pin "15") (pinfunction "O5_15") (pintype "output"))
      (node (ref "IC6") (pin "11") (pinfunction "CLK_11") (pintype "input"))
    )
    (net (code "72") (name "MEM_EN") (class "Default")
      (node (ref "IC3") (pin "16") (pinfunction "O4_16") (pintype "output"))
      (node (ref "IC7") (pin "1") (pinfunction "G_1") (pintype "input"))
    )
    (net (code "73") (name "Net-(CON1A-{slash}CS1)") (class "Default")
      (node (ref "CON1") (pin "32") (pinfunction "/CS1_32") (pintype "input"))
      (node (ref "R11") (pin "1") (pinfunction "1_1") (pintype "passive"))
    )
    (net (code "74") (name "Net-(CON1A-{slash}DASP)") (class "Default")
      (node (ref "CON1") (pin "45") (pinfunction "/DASP_45") (pintype "bidirectional"))
      (node (ref "LED1") (pin "K") (pinfunction "C_K") (pintype "passive"))
    )
    (net (code "75") (name "Net-(CON1A-{slash}PDIAG)") (class "Default")
      (node (ref "CON1") (pin "46") (pinfunction "/PDIAG_46") (pintype "bidirectional"))
      (node (ref "R10") (pin "1") (pinfunction "1_1") (pintype "passive"))
    )
    (net (code "76") (name "Net-(CON1A-{slash}REG)") (class "Default")
      (node (ref "CON1") (pin "44") (pinfunction "/REG_44") (pintype "input"))
      (node (ref "R8") (pin "1") (pinfunction "1_1") (pintype "passive"))
    )
    (net (code "77") (name "Net-(CON1A-{slash}WE)") (class "Default")
      (node (ref "CON1") (pin "36") (pinfunction "/WE_36") (pintype "input"))
      (node (ref "R7") (pin "1") (pinfunction "1_1") (pintype "passive"))
    )
    (net (code "78") (name "Net-(IC1-RST5_5)") (class "Default")
      (node (ref "IC1") (pin "9") (pinfunction "RST5_5_9") (pintype "input"))
      (node (ref "RN1") (pin "2") (pinfunction "2_2") (pintype "passive"))
    )
    (net (code "79") (name "Net-(IC1-RST6_5)") (class "Default")
      (node (ref "IC1") (pin "8") (pinfunction "RST6_5_8") (pintype "input"))
      (node (ref "RN1") (pin "3") (pinfunction "3_3") (pintype "passive"))
    )
    (net (code "80") (name "Net-(IC1-RST7_5)") (class "Default")
      (node (ref "IC1") (pin "7") (pinfunction "RST7_5_7") (pintype "input"))
      (node (ref "RN1") (pin "4") (pinfunction "4_4") (pintype "passive"))
    )
    (net (code "81") (name "Net-(IC1-TRAP)") (class "Default")
      (node (ref "IC1") (pin "6") (pinfunction "TRAP_6") (pintype "input"))
      (node (ref "RN1") (pin "5") (pinfunction "5_5") (pintype "passive"))
    )
    (net (code "82") (name "Net-(IC1-X1)") (class "Default")
      (node (ref "IC1") (pin "1") (pinfunction "X1_1") (pintype "input"))
      (node (ref "Q1") (pin "2") (pinfunction "2_2") (pintype "passive"))
    )
    (net (code "83") (name "Net-(IC1-X2)") (class "Default")
      (node (ref "C8") (pin "2") (pinfunction "2_2") (pintype "passive"))
      (node (ref "IC1") (pin "2") (pinfunction "X2_2") (pintype "input"))
      (node (ref "Q1") (pin "1") (pinfunction "1_1") (pintype "passive"))
    )
    (net (code "84") (name "Net-(IC4A-I0)") (class "Default")
      (node (ref "IC4") (pin "1") (pinfunction "I0_1") (pintype "input"))
      (node (ref "IC4") (pin "11") (pinfunction "O_11") (pintype "output"))
    )
    (net (code "85") (name "Net-(IC4B-I1)") (class "Default")
      (node (ref "IC4") (pin "5") (pinfunction "I1_5") (pintype "input"))
      (node (ref "IC4") (pin "8") (pinfunction "O_8") (pintype "output"))
    )
    (net (code "86") (name "Net-(IC6A-Q7)") (class "Default")
      (node (ref "IC6") (pin "16") (pinfunction "Q7_16") (pintype "output"))
      (node (ref "R3") (pin "1") (pinfunction "1_1") (pintype "passive"))
    )
    (net (code "87") (name "Net-(IC6A-Q8)") (class "Default")
      (node (ref "IC6") (pin "19") (pinfunction "Q8_19") (pintype "output"))
      (node (ref "R2") (pin "1") (pinfunction "1_1") (pintype "passive"))
    )
    (net (code "88") (name "Net-(IC7A-Y1)") (class "Default")
      (node (ref "IC7") (pin "15") (pinfunction "G_15") (pintype "input"))
      (node (ref "IC7") (pin "5") (pinfunction "Y1_5") (pintype "output"))
    )
    (net (code "89") (name "Net-(IC8A-PRE)") (class "Default")
      (node (ref "IC8") (pin "10") (pinfunction "PRE_10") (pintype "input"))
      (node (ref "IC8") (pin "13") (pinfunction "CLR_13") (pintype "input"))
      (node (ref "IC8") (pin "4") (pinfunction "PRE_4") (pintype "input"))
      (node (ref "R18") (pin "1") (pinfunction "1_1") (pintype "passive"))
    )
    (net (code "90") (name "Net-(JP1-Pad2)") (class "Default")
      (node (ref "JP1") (pin "2") (pinfunction "2_2") (pintype "passive"))
      (node (ref "R1") (pin "1") (pinfunction "1_1") (pintype "passive"))
    )
    (net (code "91") (name "Net-(LED1-PadA)") (class "Default")
      (node (ref "LED1") (pin "A") (pinfunction "A_A") (pintype "passive"))
      (node (ref "R5") (pin "1") (pinfunction "1_1") (pintype "passive"))
    )
    (net (code "92") (name "Net-(LED3-C)") (class "Default")
      (node (ref "LED3") (pin "K") (pinfunction "C_K") (pintype "passive"))
      (node (ref "R2") (pin "2") (pinfunction "2_2") (pintype "passive"))
    )
    (net (code "93") (name "Net-(LED4-C)") (class "Default")
      (node (ref "LED4") (pin "K") (pinfunction "C_K") (pintype "passive"))
      (node (ref "R3") (pin "2") (pinfunction "2_2") (pintype "passive"))
    )
    (net (code "94") (name "OUT_1") (class "Default")
      (node (ref "IC6") (pin "12") (pinfunction "Q5_12") (pintype "output"))
      (node (ref "SV2") (pin "3") (pinfunction "3_3") (pintype "passive"))
    )
    (net (code "95") (name "OUT_2") (class "Default")
      (node (ref "IC6") (pin "15") (pinfunction "Q6_15") (pintype "output"))
      (node (ref "SV2") (pin "4") (pinfunction "4_4") (pintype "passive"))
    )
    (net (code "96") (name "OUT_3") (class "Default")
      (node (ref "IC6") (pin "9") (pinfunction "Q4_9") (pintype "output"))
      (node (ref "SV2") (pin "5") (pinfunction "5_5") (pintype "passive"))
    )
    (net (code "97") (name "OUT_4") (class "Default")
      (node (ref "IC6") (pin "5") (pinfunction "Q2_5") (pintype "output"))
      (node (ref "SV2") (pin "6") (pinfunction "6_6") (pintype "passive"))
    )
    (net (code "98") (name "RD") (class "Default")
      (node (ref "IC1") (pin "32") (pinfunction "RD_32") (pintype "output"))
      (node (ref "IC11") (pin "1") (pinfunction "DIR_1") (pintype "input"))
      (node (ref "IC3") (pin "4") (pinfunction "I3_4") (pintype "input"))
      (node (ref "R15") (pin "1") (pinfunction "1_1") (pintype "passive"))
      (node (ref "SV2") (pin "34") (pinfunction "34_34") (pintype "passive"))
      (node (ref "U$2") (pin "22") (pinfunction "~{OE}_22") (pintype "bidirectional"))
      (node (ref "U$3") (pin "22") (pinfunction "~{RD}_22") (pintype "bidirectional"))
      (node (ref "U$4") (pin "22") (pinfunction "~{OE}_22") (pintype "bidirectional"))
    )
    (net (code "99") (name "RDYIN") (class "Default")
      (node (ref "IC1") (pin "35") (pinfunction "READY_35") (pintype "input"))
      (node (ref "R6") (pin "1") (pinfunction "1_1") (pintype "passive"))
      (node (ref "SV2") (pin "1") (pinfunction "1_1") (pintype "passive"))
    )
    (net (code "100") (name "RESET") (class "Default")
      (node (ref "IC1") (pin "3") (pinfunction "RES_OUT_3") (pintype "output"))
      (node (ref "IC3") (pin "3") (pinfunction "I2_3") (pintype "input"))
      (node (ref "SV2") (pin "31") (pinfunction "31_31") (pintype "passive"))
    )
    (net (code "101") (name "RES_IN") (class "Default")
      (node (ref "C4") (pin "1") (pinfunction "1_1") (pintype "passive"))
      (node (ref "D1") (pin "A") (pinfunction "A_A") (pintype "passive"))
      (node (ref "IC1") (pin "36") (pinfunction "RES_IN_36") (pintype "input"))
      (node (ref "R1") (pin "2") (pinfunction "2_2") (pintype "passive"))
      (node (ref "R4") (pin "1") (pinfunction "1_1") (pintype "passive"))
    )
    (net (code "102") (name "SET_BANK_A14") (class "Default")
      (node (ref "IC10") (pin "4") (pinfunction "I0_4") (pintype "input"))
      (node (ref "IC6") (pin "2") (pinfunction "Q1_2") (pintype "output"))
    )
    (net (code "103") (name "START_MEM_SWITCH") (class "Default")
      (node (ref "IC4") (pin "2") (pinfunction "I1_2") (pintype "input"))
      (node (ref "IC4") (pin "4") (pinfunction "I0_4") (pintype "input"))
      (node (ref "IC6") (pin "6") (pinfunction "Q3_6") (pintype "output"))
    )
    (net (code "104") (name "VCC") (class "Default")
      (node (ref "C1") (pin "1") (pinfunction "1_1") (pintype "passive"))
      (node (ref "C10") (pin "+") (pinfunction "+_+") (pintype "passive"))
      (node (ref "C11") (pin "1") (pinfunction "1_1") (pintype "passive"))
      (node (ref "C12") (pin "1") (pinfunction "1_1") (pintype "passive"))
      (node (ref "C13") (pin "1") (pinfunction "1_1") (pintype "passive"))
      (node (ref "C14") (pin "1") (pinfunction "1_1") (pintype "passive"))
      (node (ref "C15") (pin "1") (pinfunction "1_1") (pintype "passive"))
      (node (ref "C16") (pin "+") (pinfunction "+_+") (pintype "passive"))
      (node (ref "C18") (pin "1") (pinfunction "1_1") (pintype "passive"))
      (node (ref "C2") (pin "1") (pinfunction "1_1") (pintype "passive"))
      (node (ref "C21") (pin "1") (pinfunction "1_1") (pintype "passive"))
      (node (ref "C22") (pin "1") (pinfunction "1_1") (pintype "passive"))
      (node (ref "C23") (pin "+") (pinfunction "+_+") (pintype "passive"))
      (node (ref "C3") (pin "1") (pinfunction "1_1") (pintype "passive"))
      (node (ref "C5") (pin "1") (pinfunction "1_1") (pintype "passive"))
      (node (ref "C6") (pin "1") (pinfunction "1_1") (pintype "passive"))
      (node (ref "C7") (pin "1") (pinfunction "1_1") (pintype "passive"))
      (node (ref "C9") (pin "1") (pinfunction "1_1") (pintype "passive"))
      (node (ref "CON1") (pin "13") (pinfunction "VCC2_13") (pintype "power_in"))
      (node (ref "CON1") (pin "38") (pinfunction "VCC1_38") (pintype "power_in"))
      (node (ref "D1") (pin "C") (pinfunction "C_C") (pintype "passive"))
      (node (ref "IC1") (pin "40") (pinfunction "VCC_40") (pintype "power_in"))
      (node (ref "IC10") (pin "14") (pinfunction "VCC_14") (pintype "power_in"))
      (node (ref "IC3") (pin "20") (pinfunction "VCC_20") (pintype "power_in"))
      (node (ref "IC9") (pin "16") (pinfunction "VCC_16") (pintype "power_in"))
      (node (ref "JP3") (pin "1") (pinfunction "1_1") (pintype "passive"))
      (node (ref "LED3") (pin "A") (pinfunction "A_A") (pintype "passive"))
      (node (ref "LED4") (pin "A") (pinfunction "A_A") (pintype "passive"))
      (node (ref "R10") (pin "2") (pinfunction "2_2") (pintype "passive"))
      (node (ref "R11") (pin "2") (pinfunction "2_2") (pintype "passive"))
      (node (ref "R14") (pin "2") (pinfunction "2_2") (pintype "passive"))
      (node (ref "R15") (pin "2") (pinfunction "2_2") (pintype "passive"))
      (node (ref "R16") (pin "2") (pinfunction "2_2") (pintype "passive"))
      (node (ref "R17") (pin "1") (pinfunction "1_1") (pintype "passive"))
      (node (ref "R18") (pin "2") (pinfunction "2_2") (pintype "passive"))
      (node (ref "R4") (pin "2") (pinfunction "2_2") (pintype "passive"))
      (node (ref "R5") (pin "2") (pinfunction "2_2") (pintype "passive"))
      (node (ref "R6") (pin "2") (pinfunction "2_2") (pintype "passive"))
      (node (ref "R7") (pin "2") (pinfunction "2_2") (pintype "passive"))
      (node (ref "R8") (pin "2") (pinfunction "2_2") (pintype "passive"))
      (node (ref "U$2") (pin "28") (pinfunction "VCC_28") (pintype "bidirectional"))
      (node (ref "U$3") (pin "1") (pinfunction "VPP_1") (pintype "bidirectional"))
      (node (ref "U$3") (pin "27") (pinfunction "~{P}_27") (pintype "bidirectional"))
      (node (ref "U$3") (pin "28") (pinfunction "VCC_28") (pintype "bidirectional"))
      (node (ref "U$4") (pin "28") (pinfunction "VCC_28") (pintype "bidirectional"))
    )
    (net (code "105") (name "WR") (class "Default")
      (node (ref "IC1") (pin "31") (pinfunction "WR_31") (pintype "output"))
      (node (ref "IC3") (pin "5") (pinfunction "I4_5") (pintype "input"))
      (node (ref "R16") (pin "1") (pinfunction "1_1") (pintype "passive"))
      (node (ref "SV2") (pin "35") (pinfunction "35_35") (pintype "passive"))
      (node (ref "U$2") (pin "27") (pinfunction "~{WE}_27") (pintype "bidirectional"))
      (node (ref "U$4") (pin "27") (pinfunction "~{WE}_27") (pintype "bidirectional"))
    )
    (net (code "106") (name "unconnected-(CON1A-D08-Pad47)") (class "Default")
      (node (ref "CON1") (pin "47") (pinfunction "D08_47") (pintype "bidirectional"))
    )
    (net (code "107") (name "unconnected-(CON1A-D09-Pad48)") (class "Default")
      (node (ref "CON1") (pin "48") (pinfunction "D09_48") (pintype "bidirectional"))
    )
    (net (code "108") (name "unconnected-(CON1A-D10-Pad49)") (class "Default")
      (node (ref "CON1") (pin "49") (pinfunction "D10_49") (pintype "bidirectional"))
    )
    (net (code "109") (name "unconnected-(CON1A-D11-Pad27)") (class "Default")
      (node (ref "CON1") (pin "27") (pinfunction "D11_27") (pintype "bidirectional"))
    )
    (net (code "110") (name "unconnected-(CON1A-D12-Pad28)") (class "Default")
      (node (ref "CON1") (pin "28") (pinfunction "D12_28") (pintype "bidirectional"))
    )
    (net (code "111") (name "unconnected-(CON1A-D13-Pad29)") (class "Default")
      (node (ref "CON1") (pin "29") (pinfunction "D13_29") (pintype "bidirectional"))
    )
    (net (code "112") (name "unconnected-(CON1A-D14-Pad30)") (class "Default")
      (node (ref "CON1") (pin "30") (pinfunction "D14_30") (pintype "bidirectional"))
    )
    (net (code "113") (name "unconnected-(CON1A-D15-Pad31)") (class "Default")
      (node (ref "CON1") (pin "31") (pinfunction "D15_31") (pintype "bidirectional"))
    )
    (net (code "114") (name "unconnected-(CON1A-INTRQ-Pad37)") (class "Default")
      (node (ref "CON1") (pin "37") (pinfunction "INTRQ_37") (pintype "output"))
    )
    (net (code "115") (name "unconnected-(CON1A-IORDY-Pad42)") (class "Default")
      (node (ref "CON1") (pin "42") (pinfunction "IORDY_42") (pintype "output"))
    )
    (net (code "116") (name "unconnected-(CON1A-{slash}CD1-Pad26)") (class "Default")
      (node (ref "CON1") (pin "26") (pinfunction "/CD1_26") (pintype "output"))
    )
    (net (code "117") (name "unconnected-(CON1A-{slash}CD2-Pad25)") (class "Default")
      (node (ref "CON1") (pin "25") (pinfunction "/CD2_25") (pintype "output"))
    )
    (net (code "118") (name "unconnected-(CON1A-{slash}INPACK-Pad43)") (class "Default")
      (node (ref "CON1") (pin "43") (pinfunction "/INPACK_43") (pintype "output"))
    )
    (net (code "119") (name "unconnected-(CON1A-{slash}IOCS16-Pad24)") (class "Default")
      (node (ref "CON1") (pin "24") (pinfunction "/IOCS16_24") (pintype "output"))
    )
    (net (code "120") (name "unconnected-(CON1A-{slash}VS1-Pad33)") (class "Default")
      (node (ref "CON1") (pin "33") (pinfunction "/VS1_33") (pintype "output"))
    )
    (net (code "121") (name "unconnected-(CON1A-{slash}VS2-Pad40)") (class "Default")
      (node (ref "CON1") (pin "40") (pinfunction "/VS2_40") (pintype "output"))
    )
    (net (code "122") (name "unconnected-(IC1-S0-Pad29)") (class "Default")
      (node (ref "IC1") (pin "29") (pinfunction "S0_29") (pintype "output"))
    )
    (net (code "123") (name "unconnected-(IC1-S1-Pad33)") (class "Default")
      (node (ref "IC1") (pin "33") (pinfunction "S1_33") (pintype "output"))
    )
    (net (code "124") (name "unconnected-(IC1-SID-Pad5)") (class "Default")
      (node (ref "IC1") (pin "5") (pinfunction "SID_5") (pintype "input"))
    )
    (net (code "125") (name "unconnected-(IC1-SOD-Pad4)") (class "Default")
      (node (ref "IC1") (pin "4") (pinfunction "SOD_4") (pintype "output"))
    )
    (net (code "126") (name "unconnected-(IC3-O7-Pad13)") (class "Default")
      (node (ref "IC3") (pin "13") (pinfunction "O7_13") (pintype "output"))
    )
    (net (code "127") (name "unconnected-(IC3-O8-Pad12)") (class "Default")
      (node (ref "IC3") (pin "12") (pinfunction "O8_12") (pintype "output"))
    )
    (net (code "128") (name "unconnected-(IC3-OE-Pad11)") (class "Default")
      (node (ref "IC3") (pin "11") (pinfunction "OE_11") (pintype "input"))
    )
    (net (code "129") (name "unconnected-(IC7A-Y2-Pad6)") (class "Default")
      (node (ref "IC7") (pin "6") (pinfunction "Y2_6") (pintype "output"))
    )
    (net (code "130") (name "unconnected-(IC7A-Y3-Pad7)") (class "Default")
      (node (ref "IC7") (pin "7") (pinfunction "Y3_7") (pintype "output"))
    )
    (net (code "131") (name "unconnected-(IC7B-Y2-Pad10)") (class "Default")
      (node (ref "IC7") (pin "10") (pinfunction "Y2_10") (pintype "output"))
    )
    (net (code "132") (name "unconnected-(IC7B-Y3-Pad9)") (class "Default")
      (node (ref "IC7") (pin "9") (pinfunction "Y3_9") (pintype "output"))
    )
    (net (code "133") (name "unconnected-(IC8A-Q-Pad5)") (class "Default")
      (node (ref "IC8") (pin "5") (pinfunction "Q_5") (pintype "output"))
    )
    (net (code "134") (name "unconnected-(IC8A-~{Q}-Pad6)") (class "Default")
      (node (ref "IC8") (pin "6") (pinfunction "~{Q}_6") (pintype "output"))
    )
    (net (code "135") (name "unconnected-(IC8B-~{Q}-Pad8)") (class "Default")
      (node (ref "IC8") (pin "8") (pinfunction "~{Q}_8") (pintype "output"))
    )
    (net (code "136") (name "unconnected-(IC10C-O-Pad8)") (class "Default")
      (node (ref "IC10") (pin "8") (pinfunction "O_8") (pintype "output"))
    )
    (net (code "137") (name "unconnected-(IC10D-O-Pad11)") (class "Default")
      (node (ref "IC10") (pin "11") (pinfunction "O_11") (pintype "output"))
    )
    (net (code "138") (name "unconnected-(SV2-Pad43)") (class "Default")
      (node (ref "SV2") (pin "43") (pinfunction "43_43") (pintype "passive"))
    )
    (net (code "139") (name "unconnected-(SV2-Pad44)") (class "Default")
      (node (ref "SV2") (pin "44") (pinfunction "44_44") (pintype "passive"))
    )
    (net (code "140") (name "unconnected-(SV2-Pad45)") (class "Default")
      (node (ref "SV2") (pin "45") (pinfunction "45_45") (pintype "passive"))
    )
    (net (code "141") (name "unconnected-(SV2-Pad46)") (class "Default")
      (node (ref "SV2") (pin "46") (pinfunction "46_46") (pintype "passive"))
    )
    (net (code "142") (name "unconnected-(SV2-Pad47)") (class "Default")
      (node (ref "SV2") (pin "47") (pinfunction "47_47") (pintype "passive"))
    )
    (net (code "143") (name "unconnected-(SV2-Pad48)") (class "Default")
      (node (ref "SV2") (pin "48") (pinfunction "48_48") (pintype "passive"))
    )
    (net (code "144") (name "unconnected-(SV2-Pad49)") (class "Default")
      (node (ref "SV2") (pin "49") (pinfunction "49_49") (pintype "passive"))
    )
    (net (code "145") (name "unconnected-(SV2-Pad50)") (class "Default")
      (node (ref "SV2") (pin "50") (pinfunction "50_50") (pintype "passive"))
    )
    (net (code "146") (name "unconnected-(SV2-Pad51)") (class "Default")
      (node (ref "SV2") (pin "51") (pinfunction "51_51") (pintype "passive"))
    )
    (net (code "147") (name "unconnected-(SV2-Pad52)") (class "Default")
      (node (ref "SV2") (pin "52") (pinfunction "52_52") (pintype "passive"))
    )
    (net (code "148") (name "unconnected-(SV2-Pad53)") (class "Default")
      (node (ref "SV2") (pin "53") (pinfunction "53_53") (pintype "passive"))
    )
    (net (code "149") (name "unconnected-(SV2-Pad54)") (class "Default")
      (node (ref "SV2") (pin "54") (pinfunction "54_54") (pintype "passive"))
    )
    (net (code "150") (name "unconnected-(SV2-Pad64)") (class "Default")
      (node (ref "SV2") (pin "64") (pinfunction "64_64") (pintype "passive"))
    )
  )
)
